# quantizer_main.net
KiCad netlist of a schematic drawn in EAGLE
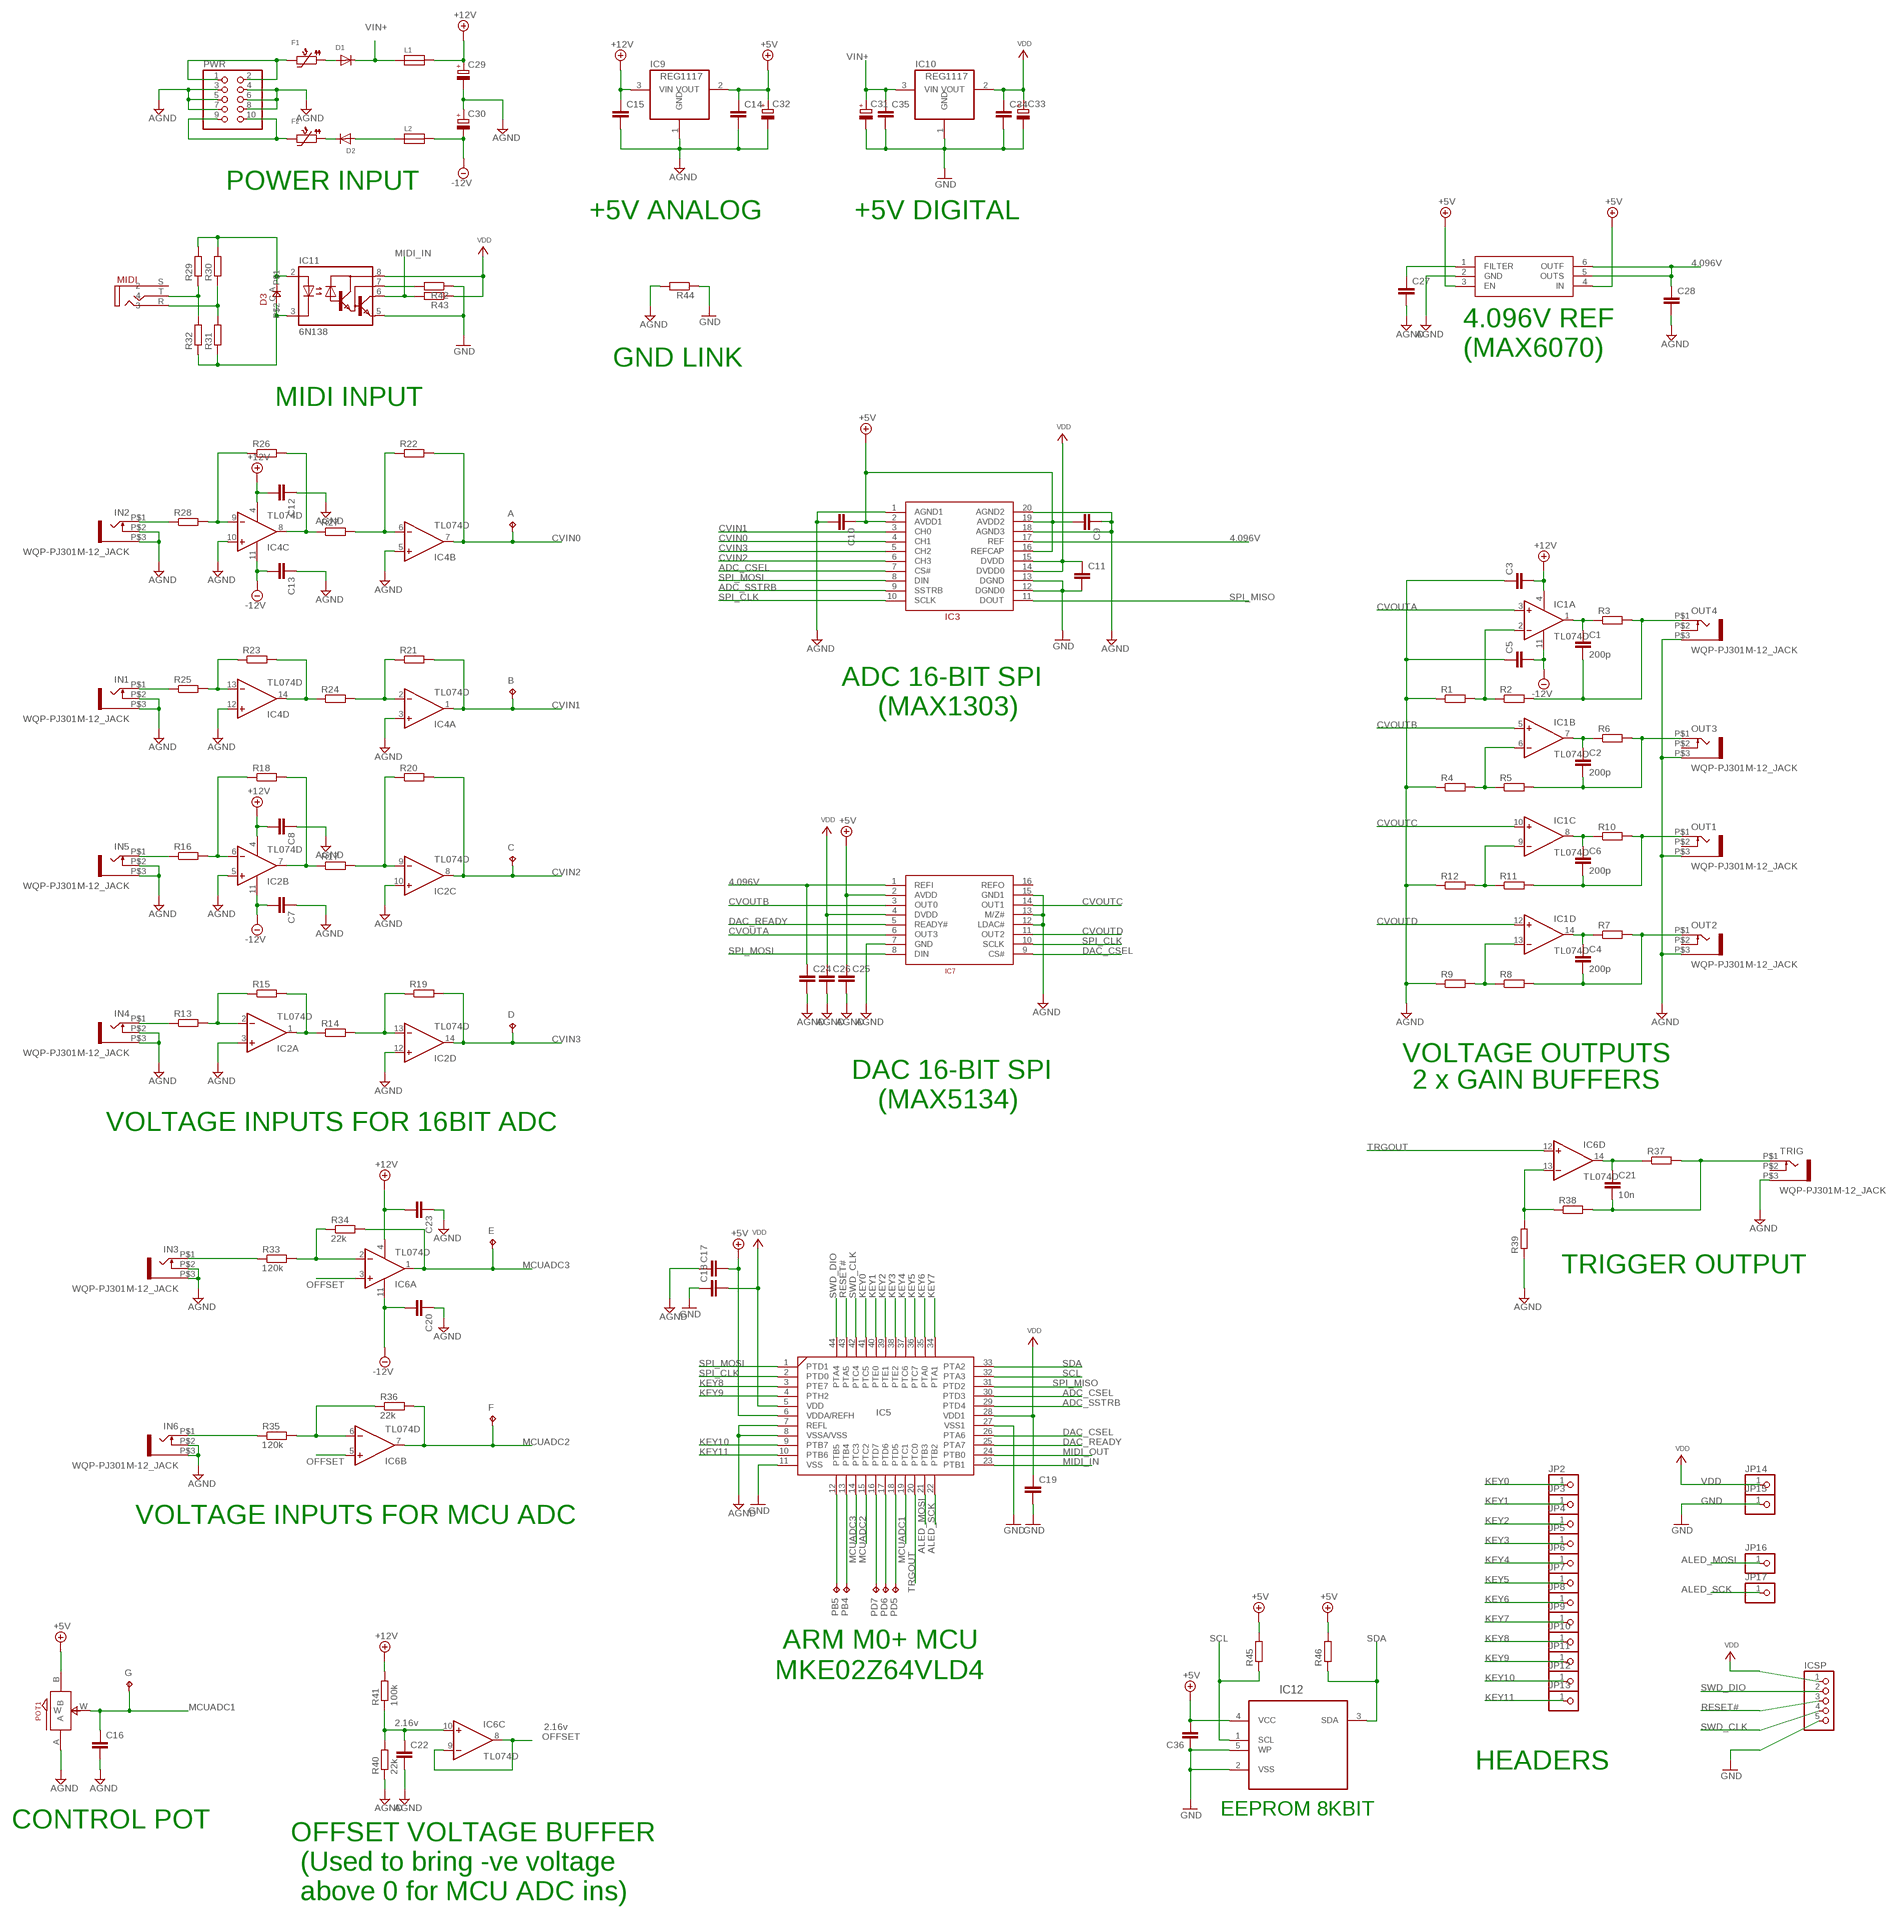
[diagram p0: schematic, sheet 1]

(export (version "E")
  (design (tool "Eeschema 10.0.6"))
  (components
    (comp (ref "A")
      (value "TPB1,27")
      (footprint "eagle-import:B1,27")
      (libsource (lib "eagle-import") (part "TPB1,27"))
    )
    (comp (ref "B")
      (value "TPB1,27")
      (footprint "eagle-import:B1,27")
      (libsource (lib "eagle-import") (part "TPB1,27"))
    )
    (comp (ref "C")
      (value "TPB1,27")
      (footprint "eagle-import:B1,27")
      (libsource (lib "eagle-import") (part "TPB1,27"))
    )
    (comp (ref "C1")
      (value "200p")
      (footprint "eagle-import:C0805")
      (libsource (lib "eagle-import") (part "C-EUC0805"))
    )
    (comp (ref "C2")
      (value "200p")
      (footprint "eagle-import:C0805")
      (libsource (lib "eagle-import") (part "C-EUC0805"))
    )
    (comp (ref "C3")
      (value "C-EUC0805")
      (footprint "eagle-import:C0805")
      (libsource (lib "eagle-import") (part "C-EUC0805"))
    )
    (comp (ref "C4")
      (value "200p")
      (footprint "eagle-import:C0805")
      (libsource (lib "eagle-import") (part "C-EUC0805"))
    )
    (comp (ref "C5")
      (value "C-EUC0805")
      (footprint "eagle-import:C0805")
      (libsource (lib "eagle-import") (part "C-EUC0805"))
    )
    (comp (ref "C6")
      (value "200p")
      (footprint "eagle-import:C0805")
      (libsource (lib "eagle-import") (part "C-EUC0805"))
    )
    (comp (ref "C7")
      (value "C-EUC0805")
      (footprint "eagle-import:C0805")
      (libsource (lib "eagle-import") (part "C-EUC0805"))
    )
    (comp (ref "C8")
      (value "C-EUC0805")
      (footprint "eagle-import:C0805")
      (libsource (lib "eagle-import") (part "C-EUC0805"))
    )
    (comp (ref "C9")
      (value "C-EUC0805")
      (footprint "eagle-import:C0805")
      (libsource (lib "eagle-import") (part "C-EUC0805"))
    )
    (comp (ref "C10")
      (value "C-EUC0805")
      (footprint "eagle-import:C0805")
      (libsource (lib "eagle-import") (part "C-EUC0805"))
    )
    (comp (ref "C11")
      (value "C-EUC0805")
      (footprint "eagle-import:C0805")
      (libsource (lib "eagle-import") (part "C-EUC0805"))
    )
    (comp (ref "C12")
      (value "C-EUC0805")
      (footprint "eagle-import:C0805")
      (libsource (lib "eagle-import") (part "C-EUC0805"))
    )
    (comp (ref "C13")
      (value "C-EUC0805")
      (footprint "eagle-import:C0805")
      (libsource (lib "eagle-import") (part "C-EUC0805"))
    )
    (comp (ref "C14")
      (value "C-EUC0805")
      (footprint "eagle-import:C0805")
      (libsource (lib "eagle-import") (part "C-EUC0805"))
    )
    (comp (ref "C15")
      (value "C-EUC0805")
      (footprint "eagle-import:C0805")
      (libsource (lib "eagle-import") (part "C-EUC0805"))
    )
    (comp (ref "C16")
      (value "C-EUC0805")
      (footprint "eagle-import:C0805")
      (libsource (lib "eagle-import") (part "C-EUC0805"))
    )
    (comp (ref "C17")
      (value "C-EUC0805")
      (footprint "eagle-import:C0805")
      (libsource (lib "eagle-import") (part "C-EUC0805"))
    )
    (comp (ref "C18")
      (value "C-EUC0805")
      (footprint "eagle-import:C0805")
      (libsource (lib "eagle-import") (part "C-EUC0805"))
    )
    (comp (ref "C19")
      (value "C-EUC0805")
      (footprint "eagle-import:C0805")
      (libsource (lib "eagle-import") (part "C-EUC0805"))
    )
    (comp (ref "C20")
      (value "C-EUC0805")
      (footprint "eagle-import:C0805")
      (libsource (lib "eagle-import") (part "C-EUC0805"))
    )
    (comp (ref "C21")
      (value "10n")
      (footprint "eagle-import:C0805")
      (libsource (lib "eagle-import") (part "C-EUC0805"))
    )
    (comp (ref "C22")
      (value "C-EUC0805")
      (footprint "eagle-import:C0805")
      (libsource (lib "eagle-import") (part "C-EUC0805"))
    )
    (comp (ref "C23")
      (value "C-EUC0805")
      (footprint "eagle-import:C0805")
      (libsource (lib "eagle-import") (part "C-EUC0805"))
    )
    (comp (ref "C24")
      (value "C-EUC0805")
      (footprint "eagle-import:C0805")
      (libsource (lib "eagle-import") (part "C-EUC0805"))
    )
    (comp (ref "C25")
      (value "C-EUC0805")
      (footprint "eagle-import:C0805")
      (libsource (lib "eagle-import") (part "C-EUC0805"))
    )
    (comp (ref "C26")
      (value "C-EUC0805")
      (footprint "eagle-import:C0805")
      (libsource (lib "eagle-import") (part "C-EUC0805"))
    )
    (comp (ref "C27")
      (value "C-EUC0805")
      (footprint "eagle-import:C0805")
      (libsource (lib "eagle-import") (part "C-EUC0805"))
    )
    (comp (ref "C28")
      (value "C-EUC0805")
      (footprint "eagle-import:C0805")
      (libsource (lib "eagle-import") (part "C-EUC0805"))
    )
    (comp (ref "C29")
      (value "CPOL-EUE2-5")
      (footprint "eagle-import:E2-5")
      (libsource (lib "eagle-import") (part "CPOL-EUE2-5"))
    )
    (comp (ref "C30")
      (value "CPOL-EUE2-5")
      (footprint "eagle-import:E2-5")
      (libsource (lib "eagle-import") (part "CPOL-EUE2-5"))
    )
    (comp (ref "C31")
      (value "CPOL-EUE2-5")
      (footprint "eagle-import:E2-5")
      (libsource (lib "eagle-import") (part "CPOL-EUE2-5"))
    )
    (comp (ref "C32")
      (value "CPOL-EUE2-5")
      (footprint "eagle-import:E2-5")
      (libsource (lib "eagle-import") (part "CPOL-EUE2-5"))
    )
    (comp (ref "C33")
      (value "CPOL-EUE2-5")
      (footprint "eagle-import:E2-5")
      (libsource (lib "eagle-import") (part "CPOL-EUE2-5"))
    )
    (comp (ref "C34")
      (value "C-EUC0805")
      (footprint "eagle-import:C0805")
      (libsource (lib "eagle-import") (part "C-EUC0805"))
    )
    (comp (ref "C35")
      (value "C-EUC0805")
      (footprint "eagle-import:C0805")
      (libsource (lib "eagle-import") (part "C-EUC0805"))
    )
    (comp (ref "C36")
      (value "C-EUC0805")
      (footprint "eagle-import:C0805")
      (libsource (lib "eagle-import") (part "resistor_C-EUC0805"))
    )
    (comp (ref "D")
      (value "TPB1,27")
      (footprint "eagle-import:B1,27")
      (libsource (lib "eagle-import") (part "TPB1,27"))
    )
    (comp (ref "D1")
      (value "DIODESOD-123")
      (footprint "eagle-import:SOD-123")
      (libsource (lib "eagle-import") (part "DIODESOD-123"))
    )
    (comp (ref "D2")
      (value "DIODESOD-123")
      (footprint "eagle-import:SOD-123")
      (libsource (lib "eagle-import") (part "DIODESOD-123"))
    )
    (comp (ref "D3")
      (value "0805DIODE")
      (footprint "eagle-import:0805DIODE")
      (libsource (lib "eagle-import") (part "0805DIODE"))
    )
    (comp (ref "E")
      (value "TPB1,27")
      (footprint "eagle-import:B1,27")
      (libsource (lib "eagle-import") (part "TPB1,27"))
    )
    (comp (ref "F")
      (value "TPB1,27")
      (footprint "eagle-import:B1,27")
      (libsource (lib "eagle-import") (part "TPB1,27"))
    )
    (comp (ref "F1")
      (value "PTC1206")
      (footprint "eagle-import:1206")
      (libsource (lib "eagle-import") (part "PTC1206"))
    )
    (comp (ref "F2")
      (value "PTC1206")
      (footprint "eagle-import:1206")
      (libsource (lib "eagle-import") (part "PTC1206"))
    )
    (comp (ref "G")
      (value "TPB1,27")
      (footprint "eagle-import:B1,27")
      (libsource (lib "eagle-import") (part "TPB1,27"))
    )
    (comp (ref "IC1")
      (value "TL074D")
      (footprint "eagle-import:SO14")
      (libsource (lib "eagle-import") (part "TL074D"))
    )
    (comp (ref "IC2")
      (value "TL074D")
      (footprint "eagle-import:SO14")
      (libsource (lib "eagle-import") (part "TL074D"))
    )
    (comp (ref "IC3")
      (value "MAX1303_ADC")
      (footprint "eagle-import:TSSOP20")
      (libsource (lib "eagle-import") (part "MAX1303_ADC"))
    )
    (comp (ref "IC4")
      (value "TL074D")
      (footprint "eagle-import:SO14")
      (libsource (lib "eagle-import") (part "TL074D"))
    )
    (comp (ref "IC5")
      (value "MKE02_44PIN")
      (footprint "eagle-import:TQFP44")
      (libsource (lib "eagle-import") (part "MKE02_44PIN"))
    )
    (comp (ref "IC6")
      (value "TL074D")
      (footprint "eagle-import:SO14")
      (libsource (lib "eagle-import") (part "TL074D"))
    )
    (comp (ref "IC7")
      (value "MAX5134_DAC")
      (footprint "eagle-import:TSSOP16")
      (libsource (lib "eagle-import") (part "MAX5134_DAC"))
    )
    (comp (ref "IC8")
      (value "MAX6070")
      (footprint "eagle-import:SOT23-6")
      (libsource (lib "eagle-import") (part "MAX6070"))
    )
    (comp (ref "IC9")
      (value "REG1117")
      (footprint "eagle-import:SOT223")
      (libsource (lib "eagle-import") (part "REG1117"))
    )
    (comp (ref "IC10")
      (value "REG1117")
      (footprint "eagle-import:SOT223")
      (libsource (lib "eagle-import") (part "REG1117"))
    )
    (comp (ref "IC11")
      (value "6N138")
      (footprint "eagle-import:DIL08")
      (fields (field (name "MF") "VISHAY/TELEFUNKEN"))
      (libsource (lib "eagle-import") (part "6N138"))
    )
    (comp (ref "IC12")
      (value "24LC_16BT-I/OT")
      (footprint "eagle-import:SOT95P290X145-5N")
      (fields (field (name "MPN") "24LC16BT-I/OT "))
      (libsource (lib "eagle-import") (part "24LC_16BT-I/OT"))
    )
    (comp (ref "ICSP")
      (value "PINHD-1X5")
      (footprint "eagle-import:1X05")
      (libsource (lib "eagle-import") (part "PINHD-1X5"))
    )
    (comp (ref "IN1")
      (value "WQP-PJ301M-12_JACK")
      (footprint "eagle-import:WQP-PJ301M-12_JACK")
      (libsource (lib "eagle-import") (part "WQP-PJ301M-12_JACK"))
    )
    (comp (ref "IN2")
      (value "WQP-PJ301M-12_JACK")
      (footprint "eagle-import:WQP-PJ301M-12_JACK")
      (libsource (lib "eagle-import") (part "WQP-PJ301M-12_JACK"))
    )
    (comp (ref "IN3")
      (value "WQP-PJ301M-12_JACK")
      (footprint "eagle-import:WQP-PJ301M-12_JACK")
      (libsource (lib "eagle-import") (part "WQP-PJ301M-12_JACK"))
    )
    (comp (ref "IN4")
      (value "WQP-PJ301M-12_JACK")
      (footprint "eagle-import:WQP-PJ301M-12_JACK")
      (libsource (lib "eagle-import") (part "WQP-PJ301M-12_JACK"))
    )
    (comp (ref "IN5")
      (value "WQP-PJ301M-12_JACK")
      (footprint "eagle-import:WQP-PJ301M-12_JACK")
      (libsource (lib "eagle-import") (part "WQP-PJ301M-12_JACK"))
    )
    (comp (ref "IN6")
      (value "WQP-PJ301M-12_JACK")
      (footprint "eagle-import:WQP-PJ301M-12_JACK")
      (libsource (lib "eagle-import") (part "WQP-PJ301M-12_JACK"))
    )
    (comp (ref "JP2")
      (value "PINHD-1X1")
      (footprint "eagle-import:1X01")
      (libsource (lib "eagle-import") (part "PINHD-1X1"))
    )
    (comp (ref "JP3")
      (value "PINHD-1X1")
      (footprint "eagle-import:1X01")
      (libsource (lib "eagle-import") (part "PINHD-1X1"))
    )
    (comp (ref "JP4")
      (value "PINHD-1X1")
      (footprint "eagle-import:1X01")
      (libsource (lib "eagle-import") (part "PINHD-1X1"))
    )
    (comp (ref "JP5")
      (value "PINHD-1X1")
      (footprint "eagle-import:1X01")
      (libsource (lib "eagle-import") (part "PINHD-1X1"))
    )
    (comp (ref "JP6")
      (value "PINHD-1X1")
      (footprint "eagle-import:1X01")
      (libsource (lib "eagle-import") (part "PINHD-1X1"))
    )
    (comp (ref "JP7")
      (value "PINHD-1X1")
      (footprint "eagle-import:1X01")
      (libsource (lib "eagle-import") (part "PINHD-1X1"))
    )
    (comp (ref "JP8")
      (value "PINHD-1X1")
      (footprint "eagle-import:1X01")
      (libsource (lib "eagle-import") (part "PINHD-1X1"))
    )
    (comp (ref "JP9")
      (value "PINHD-1X1")
      (footprint "eagle-import:1X01")
      (libsource (lib "eagle-import") (part "PINHD-1X1"))
    )
    (comp (ref "JP10")
      (value "PINHD-1X1")
      (footprint "eagle-import:1X01")
      (libsource (lib "eagle-import") (part "PINHD-1X1"))
    )
    (comp (ref "JP11")
      (value "PINHD-1X1")
      (footprint "eagle-import:1X01")
      (libsource (lib "eagle-import") (part "PINHD-1X1"))
    )
    (comp (ref "JP12")
      (value "PINHD-1X1")
      (footprint "eagle-import:1X01")
      (libsource (lib "eagle-import") (part "PINHD-1X1"))
    )
    (comp (ref "JP13")
      (value "PINHD-1X1")
      (footprint "eagle-import:1X01")
      (libsource (lib "eagle-import") (part "PINHD-1X1"))
    )
    (comp (ref "JP14")
      (value "PINHD-1X1")
      (footprint "eagle-import:1X01")
      (libsource (lib "eagle-import") (part "PINHD-1X1"))
    )
    (comp (ref "JP15")
      (value "PINHD-1X1")
      (footprint "eagle-import:1X01")
      (libsource (lib "eagle-import") (part "PINHD-1X1"))
    )
    (comp (ref "JP16")
      (value "PINHD-1X1")
      (footprint "eagle-import:1X01")
      (libsource (lib "eagle-import") (part "PINHD-1X1"))
    )
    (comp (ref "JP17")
      (value "PINHD-1X1")
      (footprint "eagle-import:1X01")
      (libsource (lib "eagle-import") (part "PINHD-1X1"))
    )
    (comp (ref "L1")
      (value "FERRITE")
      (footprint "eagle-import:0603")
      (libsource (lib "eagle-import") (part "FERRITE"))
    )
    (comp (ref "L2")
      (value "FERRITE")
      (footprint "eagle-import:0603")
      (libsource (lib "eagle-import") (part "FERRITE"))
    )
    (comp (ref "MIDI")
      (value "VERTICAL_3_5MM_SOCKETTHONK")
      (footprint "eagle-import:PJ301CM")
      (libsource (lib "eagle-import") (part "VERTICAL_3_5MM_SOCKETTHONK"))
    )
    (comp (ref "OUT1")
      (value "WQP-PJ301M-12_JACK")
      (footprint "eagle-import:WQP-PJ301M-12_JACK")
      (libsource (lib "eagle-import") (part "WQP-PJ301M-12_JACK"))
    )
    (comp (ref "OUT2")
      (value "WQP-PJ301M-12_JACK")
      (footprint "eagle-import:WQP-PJ301M-12_JACK")
      (libsource (lib "eagle-import") (part "WQP-PJ301M-12_JACK"))
    )
    (comp (ref "OUT3")
      (value "WQP-PJ301M-12_JACK")
      (footprint "eagle-import:WQP-PJ301M-12_JACK")
      (libsource (lib "eagle-import") (part "WQP-PJ301M-12_JACK"))
    )
    (comp (ref "OUT4")
      (value "WQP-PJ301M-12_JACK")
      (footprint "eagle-import:WQP-PJ301M-12_JACK")
      (libsource (lib "eagle-import") (part "WQP-PJ301M-12_JACK"))
    )
    (comp (ref "PB4")
      (value "TPB1,27")
      (footprint "eagle-import:B1,27")
      (libsource (lib "eagle-import") (part "TPB1,27"))
    )
    (comp (ref "PB5")
      (value "TPB1,27")
      (footprint "eagle-import:B1,27")
      (libsource (lib "eagle-import") (part "TPB1,27"))
    )
    (comp (ref "PD5")
      (value "TPB1,27")
      (footprint "eagle-import:B1,27")
      (libsource (lib "eagle-import") (part "TPB1,27"))
    )
    (comp (ref "PD6")
      (value "TPB1,27")
      (footprint "eagle-import:B1,27")
      (libsource (lib "eagle-import") (part "TPB1,27"))
    )
    (comp (ref "PD7")
      (value "TPB1,27")
      (footprint "eagle-import:B1,27")
      (libsource (lib "eagle-import") (part "TPB1,27"))
    )
    (comp (ref "POT1")
      (value "ALPS_POT_SMALL")
      (footprint "eagle-import:SMALL_ALPS_POT")
      (libsource (lib "eagle-import") (part "ALPS_POT_SMALL"))
    )
    (comp (ref "PWR")
      (value "PINHD-2X5")
      (footprint "eagle-import:2X05")
      (libsource (lib "eagle-import") (part "PINHD-2X5"))
    )
    (comp (ref "R1")
      (value "R-EU_R0805")
      (footprint "eagle-import:R0805")
      (libsource (lib "eagle-import") (part "R-EU_R0805"))
    )
    (comp (ref "R2")
      (value "R-EU_R0805")
      (footprint "eagle-import:R0805")
      (libsource (lib "eagle-import") (part "R-EU_R0805"))
    )
    (comp (ref "R3")
      (value "R-EU_R0805")
      (footprint "eagle-import:R0805")
      (libsource (lib "eagle-import") (part "R-EU_R0805"))
    )
    (comp (ref "R4")
      (value "R-EU_R0805")
      (footprint "eagle-import:R0805")
      (libsource (lib "eagle-import") (part "R-EU_R0805"))
    )
    (comp (ref "R5")
      (value "R-EU_R0805")
      (footprint "eagle-import:R0805")
      (libsource (lib "eagle-import") (part "R-EU_R0805"))
    )
    (comp (ref "R6")
      (value "R-EU_R0805")
      (footprint "eagle-import:R0805")
      (libsource (lib "eagle-import") (part "R-EU_R0805"))
    )
    (comp (ref "R7")
      (value "R-EU_R0805")
      (footprint "eagle-import:R0805")
      (libsource (lib "eagle-import") (part "R-EU_R0805"))
    )
    (comp (ref "R8")
      (value "R-EU_R0805")
      (footprint "eagle-import:R0805")
      (libsource (lib "eagle-import") (part "R-EU_R0805"))
    )
    (comp (ref "R9")
      (value "R-EU_R0805")
      (footprint "eagle-import:R0805")
      (libsource (lib "eagle-import") (part "R-EU_R0805"))
    )
    (comp (ref "R10")
      (value "R-EU_R0805")
      (footprint "eagle-import:R0805")
      (libsource (lib "eagle-import") (part "R-EU_R0805"))
    )
    (comp (ref "R11")
      (value "R-EU_R0805")
      (footprint "eagle-import:R0805")
      (libsource (lib "eagle-import") (part "R-EU_R0805"))
    )
    (comp (ref "R12")
      (value "R-EU_R0805")
      (footprint "eagle-import:R0805")
      (libsource (lib "eagle-import") (part "R-EU_R0805"))
    )
    (comp (ref "R13")
      (value "R-EU_R0805")
      (footprint "eagle-import:R0805")
      (libsource (lib "eagle-import") (part "R-EU_R0805"))
    )
    (comp (ref "R14")
      (value "R-EU_R0805")
      (footprint "eagle-import:R0805")
      (libsource (lib "eagle-import") (part "R-EU_R0805"))
    )
    (comp (ref "R15")
      (value "R-EU_R0805")
      (footprint "eagle-import:R0805")
      (libsource (lib "eagle-import") (part "R-EU_R0805"))
    )
    (comp (ref "R16")
      (value "R-EU_R0805")
      (footprint "eagle-import:R0805")
      (libsource (lib "eagle-import") (part "R-EU_R0805"))
    )
    (comp (ref "R17")
      (value "R-EU_R0805")
      (footprint "eagle-import:R0805")
      (libsource (lib "eagle-import") (part "R-EU_R0805"))
    )
    (comp (ref "R18")
      (value "R-EU_R0805")
      (footprint "eagle-import:R0805")
      (libsource (lib "eagle-import") (part "R-EU_R0805"))
    )
    (comp (ref "R19")
      (value "R-EU_R0805")
      (footprint "eagle-import:R0805")
      (libsource (lib "eagle-import") (part "R-EU_R0805"))
    )
    (comp (ref "R20")
      (value "R-EU_R0805")
      (footprint "eagle-import:R0805")
      (libsource (lib "eagle-import") (part "R-EU_R0805"))
    )
    (comp (ref "R21")
      (value "R-EU_R0805")
      (footprint "eagle-import:R0805")
      (libsource (lib "eagle-import") (part "R-EU_R0805"))
    )
    (comp (ref "R22")
      (value "R-EU_R0805")
      (footprint "eagle-import:R0805")
      (libsource (lib "eagle-import") (part "R-EU_R0805"))
    )
    (comp (ref "R23")
      (value "R-EU_R0805")
      (footprint "eagle-import:R0805")
      (libsource (lib "eagle-import") (part "R-EU_R0805"))
    )
    (comp (ref "R24")
      (value "R-EU_R0805")
      (footprint "eagle-import:R0805")
      (libsource (lib "eagle-import") (part "R-EU_R0805"))
    )
    (comp (ref "R25")
      (value "R-EU_R0805")
      (footprint "eagle-import:R0805")
      (libsource (lib "eagle-import") (part "R-EU_R0805"))
    )
    (comp (ref "R26")
      (value "R-EU_R0805")
      (footprint "eagle-import:R0805")
      (libsource (lib "eagle-import") (part "R-EU_R0805"))
    )
    (comp (ref "R27")
      (value "R-EU_R0805")
      (footprint "eagle-import:R0805")
      (libsource (lib "eagle-import") (part "R-EU_R0805"))
    )
    (comp (ref "R28")
      (value "R-EU_R0805")
      (footprint "eagle-import:R0805")
      (libsource (lib "eagle-import") (part "R-EU_R0805"))
    )
    (comp (ref "R29")
      (value "R-EU_R0805")
      (footprint "eagle-import:R0805")
      (libsource (lib "eagle-import") (part "R-EU_R0805"))
    )
    (comp (ref "R30")
      (value "R-EU_R0805")
      (footprint "eagle-import:R0805")
      (libsource (lib "eagle-import") (part "R-EU_R0805"))
    )
    (comp (ref "R31")
      (value "R-EU_R0805")
      (footprint "eagle-import:R0805")
      (libsource (lib "eagle-import") (part "R-EU_R0805"))
    )
    (comp (ref "R32")
      (value "R-EU_R0805")
      (footprint "eagle-import:R0805")
      (libsource (lib "eagle-import") (part "R-EU_R0805"))
    )
    (comp (ref "R33")
      (value "120k")
      (footprint "eagle-import:R0805")
      (libsource (lib "eagle-import") (part "R-EU_R0805"))
    )
    (comp (ref "R34")
      (value "22k")
      (footprint "eagle-import:R0805")
      (libsource (lib "eagle-import") (part "R-EU_R0805"))
    )
    (comp (ref "R35")
      (value "120k")
      (footprint "eagle-import:R0805")
      (libsource (lib "eagle-import") (part "R-EU_R0805"))
    )
    (comp (ref "R36")
      (value "22k")
      (footprint "eagle-import:R0805")
      (libsource (lib "eagle-import") (part "R-EU_R0805"))
    )
    (comp (ref "R37")
      (value "R-EU_R0805")
      (footprint "eagle-import:R0805")
      (libsource (lib "eagle-import") (part "R-EU_R0805"))
    )
    (comp (ref "R38")
      (value "R-EU_R0805")
      (footprint "eagle-import:R0805")
      (libsource (lib "eagle-import") (part "R-EU_R0805"))
    )
    (comp (ref "R39")
      (value "R-EU_R0805")
      (footprint "eagle-import:R0805")
      (libsource (lib "eagle-import") (part "R-EU_R0805"))
    )
    (comp (ref "R40")
      (value "22k")
      (footprint "eagle-import:R0805")
      (libsource (lib "eagle-import") (part "R-EU_R0805"))
    )
    (comp (ref "R41")
      (value "100k")
      (footprint "eagle-import:R0805")
      (libsource (lib "eagle-import") (part "R-EU_R0805"))
    )
    (comp (ref "R42")
      (value "R-EU_R0805")
      (footprint "eagle-import:R0805")
      (libsource (lib "eagle-import") (part "R-EU_R0805"))
    )
    (comp (ref "R43")
      (value "R-EU_R0805")
      (footprint "eagle-import:R0805")
      (libsource (lib "eagle-import") (part "R-EU_R0805"))
    )
    (comp (ref "R44")
      (value "R-EU_R0805")
      (footprint "eagle-import:R0805")
      (libsource (lib "eagle-import") (part "R-EU_R0805"))
    )
    (comp (ref "R45")
      (value "R-EU_R0805")
      (footprint "eagle-import:R0805")
      (libsource (lib "eagle-import") (part "R-EU_R0805"))
    )
    (comp (ref "R46")
      (value "R-EU_R0805")
      (footprint "eagle-import:R0805")
      (libsource (lib "eagle-import") (part "R-EU_R0805"))
    )
    (comp (ref "TRIG")
      (value "WQP-PJ301M-12_JACK")
      (footprint "eagle-import:WQP-PJ301M-12_JACK")
      (libsource (lib "eagle-import") (part "WQP-PJ301M-12_JACK"))
    )
  )
  (nets
    (net (code "1") (name "+5V") (class "Default")
      (node (ref "C10") (pin "1") (pinfunction "1_1") (pintype "passive"))
      (node (ref "C14") (pin "1") (pinfunction "1_1") (pintype "passive"))
      (node (ref "C17") (pin "2") (pinfunction "2_2") (pintype "passive"))
      (node (ref "C25") (pin "1") (pinfunction "1_1") (pintype "passive"))
      (node (ref "C32") (pin "+") (pinfunction "+_+") (pintype "passive"))
      (node (ref "C36") (pin "2") (pinfunction "2_2") (pintype "passive"))
      (node (ref "C9") (pin "2") (pinfunction "2_2") (pintype "passive"))
      (node (ref "IC12") (pin "4") (pinfunction "VCC_4") (pintype "power_in"))
      (node (ref "IC3") (pin "16") (pinfunction "REFCAP_16") (pintype "bidirectional"))
      (node (ref "IC3") (pin "19") (pinfunction "AVDD2_19") (pintype "bidirectional"))
      (node (ref "IC3") (pin "2") (pinfunction "AVDD1_2") (pintype "bidirectional"))
      (node (ref "IC5") (pin "6") (pinfunction "VDDA/REFH_6") (pintype "bidirectional"))
      (node (ref "IC7") (pin "2") (pinfunction "AVDD_2") (pintype "bidirectional"))
      (node (ref "IC8") (pin "3") (pinfunction "EN_3") (pintype "bidirectional"))
      (node (ref "IC8") (pin "4") (pinfunction "IN_4") (pintype "bidirectional"))
      (node (ref "IC9") (pin "2") (pinfunction "VOUT_2") (pintype "output"))
      (node (ref "POT1") (pin "B") (pinfunction "B_B") (pintype "bidirectional"))
      (node (ref "R45") (pin "2") (pinfunction "2_2") (pintype "passive"))
      (node (ref "R46") (pin "2") (pinfunction "2_2") (pintype "passive"))
    )
    (net (code "2") (name "+12V") (class "Default")
      (node (ref "C12") (pin "2") (pinfunction "2_2") (pintype "passive"))
      (node (ref "C15") (pin "1") (pinfunction "1_1") (pintype "passive"))
      (node (ref "C23") (pin "2") (pinfunction "2_2") (pintype "passive"))
      (node (ref "C29") (pin "+") (pinfunction "+_+") (pintype "passive"))
      (node (ref "C3") (pin "2") (pinfunction "2_2") (pintype "passive"))
      (node (ref "C8") (pin "2") (pinfunction "2_2") (pintype "passive"))
      (node (ref "IC1") (pin "4") (pinfunction "V+_4") (pintype "power_in"))
      (node (ref "IC2") (pin "4") (pinfunction "V+_4") (pintype "power_in"))
      (node (ref "IC4") (pin "4") (pinfunction "V+_4") (pintype "power_in"))
      (node (ref "IC6") (pin "4") (pinfunction "V+_4") (pintype "power_in"))
      (node (ref "IC9") (pin "3") (pinfunction "VIN_3") (pintype "input"))
      (node (ref "L1") (pin "2") (pinfunction "P$2_2") (pintype "bidirectional"))
      (node (ref "R41") (pin "2") (pinfunction "2_2") (pintype "passive"))
    )
    (net (code "3") (name "-12V") (class "Default")
      (node (ref "C13") (pin "2") (pinfunction "2_2") (pintype "passive"))
      (node (ref "C20") (pin "2") (pinfunction "2_2") (pintype "passive"))
      (node (ref "C30") (pin "-") (pinfunction "-_-") (pintype "passive"))
      (node (ref "C5") (pin "2") (pinfunction "2_2") (pintype "passive"))
      (node (ref "C7") (pin "2") (pinfunction "2_2") (pintype "passive"))
      (node (ref "IC1") (pin "11") (pinfunction "V-_11") (pintype "power_in"))
      (node (ref "IC2") (pin "11") (pinfunction "V-_11") (pintype "power_in"))
      (node (ref "IC4") (pin "11") (pinfunction "V-_11") (pintype "power_in"))
      (node (ref "IC6") (pin "11") (pinfunction "V-_11") (pintype "power_in"))
      (node (ref "L2") (pin "2") (pinfunction "P$2_2") (pintype "bidirectional"))
    )
    (net (code "4") (name "/4.096V") (class "Default")
      (node (ref "C24") (pin "1") (pinfunction "1_1") (pintype "passive"))
      (node (ref "C28") (pin "1") (pinfunction "1_1") (pintype "passive"))
      (node (ref "IC3") (pin "17") (pinfunction "REF_17") (pintype "bidirectional"))
      (node (ref "IC7") (pin "1") (pinfunction "REFI_1") (pintype "bidirectional"))
      (node (ref "IC8") (pin "5") (pinfunction "OUTS_5") (pintype "bidirectional"))
      (node (ref "IC8") (pin "6") (pinfunction "OUTF_6") (pintype "bidirectional"))
    )
    (net (code "5") (name "/ADC_CSEL") (class "Default")
      (node (ref "IC3") (pin "7") (pinfunction "CS#_7") (pintype "bidirectional"))
      (node (ref "IC5") (pin "30") (pinfunction "PTD3_30") (pintype "bidirectional"))
    )
    (net (code "6") (name "/ADC_SSTRB") (class "Default")
      (node (ref "IC3") (pin "9") (pinfunction "SSTRB_9") (pintype "bidirectional"))
      (node (ref "IC5") (pin "29") (pinfunction "PTD4_29") (pintype "bidirectional"))
    )
    (net (code "7") (name "/ALED_MOSI") (class "Default")
      (node (ref "IC5") (pin "21") (pinfunction "PTB3_21") (pintype "bidirectional"))
      (node (ref "JP16") (pin "1") (pinfunction "1_1") (pintype "passive"))
    )
    (net (code "8") (name "/ALED_SCK") (class "Default")
      (node (ref "IC5") (pin "22") (pinfunction "PTB2_22") (pintype "bidirectional"))
      (node (ref "JP17") (pin "1") (pinfunction "1_1") (pintype "passive"))
    )
    (net (code "9") (name "/CVIN0") (class "Default")
      (node (ref "A") (pin "TP") (pinfunction "TP_TP") (pintype "input"))
      (node (ref "IC3") (pin "4") (pinfunction "CH1_4") (pintype "bidirectional"))
      (node (ref "IC4") (pin "7") (pinfunction "OUT_7") (pintype "output"))
      (node (ref "R22") (pin "2") (pinfunction "2_2") (pintype "passive"))
    )
    (net (code "10") (name "/CVIN1") (class "Default")
      (node (ref "B") (pin "TP") (pinfunction "TP_TP") (pintype "input"))
      (node (ref "IC3") (pin "3") (pinfunction "CH0_3") (pintype "bidirectional"))
      (node (ref "IC4") (pin "1") (pinfunction "OUT_1") (pintype "output"))
      (node (ref "R21") (pin "2") (pinfunction "2_2") (pintype "passive"))
    )
    (net (code "11") (name "/CVIN2") (class "Default")
      (node (ref "C") (pin "TP") (pinfunction "TP_TP") (pintype "input"))
      (node (ref "IC2") (pin "8") (pinfunction "OUT_8") (pintype "output"))
      (node (ref "IC3") (pin "6") (pinfunction "CH3_6") (pintype "bidirectional"))
      (node (ref "R20") (pin "2") (pinfunction "2_2") (pintype "passive"))
    )
    (net (code "12") (name "/CVIN3") (class "Default")
      (node (ref "D") (pin "TP") (pinfunction "TP_TP") (pintype "input"))
      (node (ref "IC2") (pin "14") (pinfunction "OUT_14") (pintype "output"))
      (node (ref "IC3") (pin "5") (pinfunction "CH2_5") (pintype "bidirectional"))
      (node (ref "R19") (pin "2") (pinfunction "2_2") (pintype "passive"))
    )
    (net (code "13") (name "/CVOUTA") (class "Default")
      (node (ref "IC1") (pin "3") (pinfunction "+IN_3") (pintype "input"))
      (node (ref "IC7") (pin "6") (pinfunction "OUT3_6") (pintype "bidirectional"))
    )
    (net (code "14") (name "/CVOUTB") (class "Default")
      (node (ref "IC1") (pin "5") (pinfunction "+IN_5") (pintype "input"))
      (node (ref "IC7") (pin "3") (pinfunction "OUT0_3") (pintype "bidirectional"))
    )
    (net (code "15") (name "/CVOUTC") (class "Default")
      (node (ref "IC1") (pin "10") (pinfunction "+IN_10") (pintype "input"))
      (node (ref "IC7") (pin "14") (pinfunction "OUT1_14") (pintype "bidirectional"))
    )
    (net (code "16") (name "/CVOUTD") (class "Default")
      (node (ref "IC1") (pin "12") (pinfunction "+IN_12") (pintype "input"))
      (node (ref "IC7") (pin "11") (pinfunction "OUT2_11") (pintype "bidirectional"))
    )
    (net (code "17") (name "/DAC_CSEL") (class "Default")
      (node (ref "IC5") (pin "26") (pinfunction "PTA6_26") (pintype "bidirectional"))
      (node (ref "IC7") (pin "9") (pinfunction "CS#_9") (pintype "bidirectional"))
    )
    (net (code "18") (name "/DAC_READY") (class "Default")
      (node (ref "IC5") (pin "25") (pinfunction "PTA7_25") (pintype "bidirectional"))
      (node (ref "IC7") (pin "5") (pinfunction "READY#_5") (pintype "bidirectional"))
    )
    (net (code "19") (name "/KEY0") (class "Default")
      (node (ref "IC5") (pin "41") (pinfunction "PTC5_41") (pintype "bidirectional"))
      (node (ref "JP2") (pin "1") (pinfunction "1_1") (pintype "passive"))
    )
    (net (code "20") (name "/KEY1") (class "Default")
      (node (ref "IC5") (pin "40") (pinfunction "PTE0_40") (pintype "bidirectional"))
      (node (ref "JP3") (pin "1") (pinfunction "1_1") (pintype "passive"))
    )
    (net (code "21") (name "/KEY2") (class "Default")
      (node (ref "IC5") (pin "39") (pinfunction "PTE1_39") (pintype "bidirectional"))
      (node (ref "JP4") (pin "1") (pinfunction "1_1") (pintype "passive"))
    )
    (net (code "22") (name "/KEY3") (class "Default")
      (node (ref "IC5") (pin "38") (pinfunction "PTE2_38") (pintype "bidirectional"))
      (node (ref "JP5") (pin "1") (pinfunction "1_1") (pintype "passive"))
    )
    (net (code "23") (name "/KEY4") (class "Default")
      (node (ref "IC5") (pin "37") (pinfunction "PTC6_37") (pintype "bidirectional"))
      (node (ref "JP6") (pin "1") (pinfunction "1_1") (pintype "passive"))
    )
    (net (code "24") (name "/KEY5") (class "Default")
      (node (ref "IC5") (pin "36") (pinfunction "PTC7_36") (pintype "bidirectional"))
      (node (ref "JP7") (pin "1") (pinfunction "1_1") (pintype "passive"))
    )
    (net (code "25") (name "/KEY6") (class "Default")
      (node (ref "IC5") (pin "35") (pinfunction "PTA0_35") (pintype "bidirectional"))
      (node (ref "JP8") (pin "1") (pinfunction "1_1") (pintype "passive"))
    )
    (net (code "26") (name "/KEY7") (class "Default")
      (node (ref "IC5") (pin "34") (pinfunction "PTA1_34") (pintype "bidirectional"))
      (node (ref "JP9") (pin "1") (pinfunction "1_1") (pintype "passive"))
    )
    (net (code "27") (name "/KEY8") (class "Default")
      (node (ref "IC5") (pin "3") (pinfunction "PTE7_3") (pintype "bidirectional"))
      (node (ref "JP10") (pin "1") (pinfunction "1_1") (pintype "passive"))
    )
    (net (code "28") (name "/KEY9") (class "Default")
      (node (ref "IC5") (pin "4") (pinfunction "PTH2_4") (pintype "bidirectional"))
      (node (ref "JP11") (pin "1") (pinfunction "1_1") (pintype "passive"))
    )
    (net (code "29") (name "/KEY10") (class "Default")
      (node (ref "IC5") (pin "9") (pinfunction "PTB7_9") (pintype "bidirectional"))
      (node (ref "JP12") (pin "1") (pinfunction "1_1") (pintype "passive"))
    )
    (net (code "30") (name "/KEY11") (class "Default")
      (node (ref "IC5") (pin "10") (pinfunction "PTB6_10") (pintype "bidirectional"))
      (node (ref "JP13") (pin "1") (pinfunction "1_1") (pintype "passive"))
    )
    (net (code "31") (name "/MCUADC1") (class "Default")
      (node (ref "C16") (pin "1") (pinfunction "1_1") (pintype "passive"))
      (node (ref "G") (pin "TP") (pinfunction "TP_TP") (pintype "input"))
      (node (ref "IC5") (pin "19") (pinfunction "PTC1_19") (pintype "bidirectional"))
      (node (ref "POT1") (pin "W") (pinfunction "W_W") (pintype "bidirectional"))
    )
    (net (code "32") (name "/MCUADC2") (class "Default")
      (node (ref "F") (pin "TP") (pinfunction "TP_TP") (pintype "input"))
      (node (ref "IC5") (pin "15") (pinfunction "PTC2_15") (pintype "bidirectional"))
      (node (ref "IC6") (pin "7") (pinfunction "OUT_7") (pintype "output"))
      (node (ref "R36") (pin "2") (pinfunction "2_2") (pintype "passive"))
    )
    (net (code "33") (name "/MCUADC3") (class "Default")
      (node (ref "E") (pin "TP") (pinfunction "TP_TP") (pintype "input"))
      (node (ref "IC5") (pin "14") (pinfunction "PTC3_14") (pintype "bidirectional"))
      (node (ref "IC6") (pin "1") (pinfunction "OUT_1") (pintype "output"))
      (node (ref "R34") (pin "2") (pinfunction "2_2") (pintype "passive"))
    )
    (net (code "34") (name "/MIDI_IN") (class "Default")
      (node (ref "IC11") (pin "6") (pinfunction "VO_6") (pintype "passive"))
      (node (ref "IC5") (pin "23") (pinfunction "PTB1_23") (pintype "bidirectional"))
      (node (ref "R43") (pin "2") (pinfunction "2_2") (pintype "passive"))
    )
    (net (code "35") (name "/MIDI_OUT") (class "Default")
      (node (ref "IC5") (pin "24") (pinfunction "PTB0_24") (pintype "bidirectional"))
    )
    (net (code "36") (name "/OFFSET") (class "Default")
      (node (ref "IC6") (pin "3") (pinfunction "+IN_3") (pintype "input"))
      (node (ref "IC6") (pin "5") (pinfunction "+IN_5") (pintype "input"))
      (node (ref "IC6") (pin "8") (pinfunction "OUT_8") (pintype "output"))
      (node (ref "IC6") (pin "9") (pinfunction "-IN_9") (pintype "input"))
    )
    (net (code "37") (name "/RESET#") (class "Default")
      (node (ref "IC5") (pin "43") (pinfunction "PTA5_43") (pintype "bidirectional"))
      (node (ref "ICSP") (pin "3") (pinfunction "3_3") (pintype "passive"))
    )
    (net (code "38") (name "/SCL") (class "Default")
      (node (ref "IC12") (pin "1") (pinfunction "SCL_1") (pintype "input"))
      (node (ref "IC5") (pin "32") (pinfunction "PTA3_32") (pintype "bidirectional"))
      (node (ref "R45") (pin "1") (pinfunction "1_1") (pintype "passive"))
    )
    (net (code "39") (name "/SDA") (class "Default")
      (node (ref "IC12") (pin "3") (pinfunction "SDA_3") (pintype "bidirectional"))
      (node (ref "IC5") (pin "33") (pinfunction "PTA2_33") (pintype "bidirectional"))
      (node (ref "R46") (pin "1") (pinfunction "1_1") (pintype "passive"))
    )
    (net (code "40") (name "/SPI_CLK") (class "Default")
      (node (ref "IC3") (pin "10") (pinfunction "SCLK_10") (pintype "bidirectional"))
      (node (ref "IC5") (pin "2") (pinfunction "PTD0_2") (pintype "bidirectional"))
      (node (ref "IC7") (pin "10") (pinfunction "SCLK_10") (pintype "bidirectional"))
    )
    (net (code "41") (name "/SPI_MISO") (class "Default")
      (node (ref "IC3") (pin "11") (pinfunction "DOUT_11") (pintype "bidirectional"))
      (node (ref "IC5") (pin "31") (pinfunction "PTD2_31") (pintype "bidirectional"))
    )
    (net (code "42") (name "/SPI_MOSI") (class "Default")
      (node (ref "IC3") (pin "8") (pinfunction "DIN_8") (pintype "bidirectional"))
      (node (ref "IC5") (pin "1") (pinfunction "PTD1_1") (pintype "bidirectional"))
      (node (ref "IC7") (pin "8") (pinfunction "DIN_8") (pintype "bidirectional"))
    )
    (net (code "43") (name "/SWD_CLK") (class "Default")
      (node (ref "IC5") (pin "42") (pinfunction "PTC4_42") (pintype "bidirectional"))
      (node (ref "ICSP") (pin "4") (pinfunction "4_4") (pintype "passive"))
    )
    (net (code "44") (name "/SWD_DIO") (class "Default")
      (node (ref "IC5") (pin "44") (pinfunction "PTA4_44") (pintype "bidirectional"))
      (node (ref "ICSP") (pin "2") (pinfunction "2_2") (pintype "passive"))
    )
    (net (code "45") (name "/TRGOUT") (class "Default")
      (node (ref "IC5") (pin "20") (pinfunction "PTC0_20") (pintype "bidirectional"))
      (node (ref "IC6") (pin "12") (pinfunction "+IN_12") (pintype "input"))
    )
    (net (code "46") (name "/VIN+") (class "Default")
      (node (ref "C31") (pin "+") (pinfunction "+_+") (pintype "passive"))
      (node (ref "C35") (pin "1") (pinfunction "1_1") (pintype "passive"))
      (node (ref "D1") (pin "C") (pinfunction "C_C") (pintype "passive"))
      (node (ref "IC10") (pin "3") (pinfunction "VIN_3") (pintype "input"))
      (node (ref "L1") (pin "1") (pinfunction "P$1_1") (pintype "bidirectional"))
    )
    (net (code "47") (name "AGND") (class "Default")
      (node (ref "C10") (pin "2") (pinfunction "2_2") (pintype "passive"))
      (node (ref "C12") (pin "1") (pinfunction "1_1") (pintype "passive"))
      (node (ref "C13") (pin "1") (pinfunction "1_1") (pintype "passive"))
      (node (ref "C14") (pin "2") (pinfunction "2_2") (pintype "passive"))
      (node (ref "C15") (pin "2") (pinfunction "2_2") (pintype "passive"))
      (node (ref "C16") (pin "2") (pinfunction "2_2") (pintype "passive"))
      (node (ref "C17") (pin "1") (pinfunction "1_1") (pintype "passive"))
      (node (ref "C20") (pin "1") (pinfunction "1_1") (pintype "passive"))
      (node (ref "C22") (pin "2") (pinfunction "2_2") (pintype "passive"))
      (node (ref "C23") (pin "1") (pinfunction "1_1") (pintype "passive"))
      (node (ref "C24") (pin "2") (pinfunction "2_2") (pintype "passive"))
      (node (ref "C25") (pin "2") (pinfunction "2_2") (pintype "passive"))
      (node (ref "C26") (pin "2") (pinfunction "2_2") (pintype "passive"))
      (node (ref "C27") (pin "2") (pinfunction "2_2") (pintype "passive"))
      (node (ref "C28") (pin "2") (pinfunction "2_2") (pintype "passive"))
      (node (ref "C29") (pin "-") (pinfunction "-_-") (pintype "passive"))
      (node (ref "C3") (pin "1") (pinfunction "1_1") (pintype "passive"))
      (node (ref "C30") (pin "+") (pinfunction "+_+") (pintype "passive"))
      (node (ref "C32") (pin "-") (pinfunction "-_-") (pintype "passive"))
      (node (ref "C5") (pin "1") (pinfunction "1_1") (pintype "passive"))
      (node (ref "C7") (pin "1") (pinfunction "1_1") (pintype "passive"))
      (node (ref "C8") (pin "1") (pinfunction "1_1") (pintype "passive"))
      (node (ref "C9") (pin "1") (pinfunction "1_1") (pintype "passive"))
      (node (ref "IC2") (pin "10") (pinfunction "+IN_10") (pintype "input"))
      (node (ref "IC2") (pin "12") (pinfunction "+IN_12") (pintype "input"))
      (node (ref "IC2") (pin "3") (pinfunction "+IN_3") (pintype "input"))
      (node (ref "IC2") (pin "5") (pinfunction "+IN_5") (pintype "input"))
      (node (ref "IC3") (pin "1") (pinfunction "AGND1_1") (pintype "bidirectional"))
      (node (ref "IC3") (pin "18") (pinfunction "AGND3_18") (pintype "bidirectional"))
      (node (ref "IC3") (pin "20") (pinfunction "AGND2_20") (pintype "bidirectional"))
      (node (ref "IC4") (pin "10") (pinfunction "+IN_10") (pintype "input"))
      (node (ref "IC4") (pin "12") (pinfunction "+IN_12") (pintype "input"))
      (node (ref "IC4") (pin "3") (pinfunction "+IN_3") (pintype "input"))
      (node (ref "IC4") (pin "5") (pinfunction "+IN_5") (pintype "input"))
      (node (ref "IC5") (pin "7") (pinfunction "REFL_7") (pintype "bidirectional"))
      (node (ref "IC5") (pin "8") (pinfunction "VSSA/VSS_8") (pintype "power_in"))
      (node (ref "IC7") (pin "12") (pinfunction "LDAC#_12") (pintype "bidirectional"))
      (node (ref "IC7") (pin "13") (pinfunction "M/Z#_13") (pintype "bidirectional"))
      (node (ref "IC7") (pin "15") (pinfunction "GND1_15") (pintype "bidirectional"))
      (node (ref "IC7") (pin "7") (pinfunction "GND_7") (pintype "bidirectional"))
      (node (ref "IC8") (pin "2") (pinfunction "GND_2") (pintype "bidirectional"))
      (node (ref "IC9") (pin "1") (pinfunction "GND_1") (pintype "power_in"))
      (node (ref "IN1") (pin "P$2") (pinfunction "3_P$2") (pintype "passive"))
      (node (ref "IN1") (pin "P$3") (pinfunction "1_P$3") (pintype "passive"))
      (node (ref "IN2") (pin "P$2") (pinfunction "3_P$2") (pintype "passive"))
      (node (ref "IN2") (pin "P$3") (pinfunction "1_P$3") (pintype "passive"))
      (node (ref "IN3") (pin "P$2") (pinfunction "3_P$2") (pintype "passive"))
      (node (ref "IN3") (pin "P$3") (pinfunction "1_P$3") (pintype "passive"))
      (node (ref "IN4") (pin "P$2") (pinfunction "3_P$2") (pintype "passive"))
      (node (ref "IN4") (pin "P$3") (pinfunction "1_P$3") (pintype "passive"))
      (node (ref "IN5") (pin "P$2") (pinfunction "3_P$2") (pintype "passive"))
      (node (ref "IN5") (pin "P$3") (pinfunction "1_P$3") (pintype "passive"))
      (node (ref "IN6") (pin "P$2") (pinfunction "3_P$2") (pintype "passive"))
      (node (ref "IN6") (pin "P$3") (pinfunction "1_P$3") (pintype "passive"))
      (node (ref "OUT1") (pin "P$3") (pinfunction "1_P$3") (pintype "passive"))
      (node (ref "OUT2") (pin "P$3") (pinfunction "1_P$3") (pintype "passive"))
      (node (ref "OUT3") (pin "P$3") (pinfunction "1_P$3") (pintype "passive"))
      (node (ref "OUT4") (pin "P$3") (pinfunction "1_P$3") (pintype "passive"))
      (node (ref "POT1") (pin "A") (pinfunction "A_A") (pintype "bidirectional"))
      (node (ref "PWR") (pin "3") (pinfunction "3_3") (pintype "passive"))
      (node (ref "PWR") (pin "4") (pinfunction "4_4") (pintype "passive"))
      (node (ref "PWR") (pin "5") (pinfunction "5_5") (pintype "passive"))
      (node (ref "PWR") (pin "6") (pinfunction "6_6") (pintype "passive"))
      (node (ref "PWR") (pin "7") (pinfunction "7_7") (pintype "passive"))
      (node (ref "PWR") (pin "8") (pinfunction "8_8") (pintype "passive"))
      (node (ref "R1") (pin "1") (pinfunction "1_1") (pintype "passive"))
      (node (ref "R12") (pin "1") (pinfunction "1_1") (pintype "passive"))
      (node (ref "R39") (pin "1") (pinfunction "1_1") (pintype "passive"))
      (node (ref "R4") (pin "1") (pinfunction "1_1") (pintype "passive"))
      (node (ref "R40") (pin "1") (pinfunction "1_1") (pintype "passive"))
      (node (ref "R44") (pin "2") (pinfunction "2_2") (pintype "passive"))
      (node (ref "R9") (pin "1") (pinfunction "1_1") (pintype "passive"))
      (node (ref "TRIG") (pin "P$3") (pinfunction "1_P$3") (pintype "passive"))
    )
    (net (code "48") (name "GND") (class "Default")
      (node (ref "C11") (pin "2") (pinfunction "2_2") (pintype "passive"))
      (node (ref "C18") (pin "1") (pinfunction "1_1") (pintype "passive"))
      (node (ref "C19") (pin "2") (pinfunction "2_2") (pintype "passive"))
      (node (ref "C31") (pin "-") (pinfunction "-_-") (pintype "passive"))
      (node (ref "C33") (pin "-") (pinfunction "-_-") (pintype "passive"))
      (node (ref "C34") (pin "2") (pinfunction "2_2") (pintype "passive"))
      (node (ref "C35") (pin "2") (pinfunction "2_2") (pintype "passive"))
      (node (ref "C36") (pin "1") (pinfunction "1_1") (pintype "passive"))
      (node (ref "IC10") (pin "1") (pinfunction "GND_1") (pintype "power_in"))
      (node (ref "IC11") (pin "5") (pinfunction "GND_5") (pintype "passive"))
      (node (ref "IC12") (pin "2") (pinfunction "VSS_2") (pintype "passive"))
      (node (ref "IC12") (pin "5") (pinfunction "WP_5") (pintype "input"))
      (node (ref "IC3") (pin "12") (pinfunction "DGND0_12") (pintype "bidirectional"))
      (node (ref "IC3") (pin "13") (pinfunction "DGND_13") (pintype "bidirectional"))
      (node (ref "IC5") (pin "11") (pinfunction "VSS_11") (pintype "power_in"))
      (node (ref "IC5") (pin "27") (pinfunction "VSS1_27") (pintype "power_in"))
      (node (ref "ICSP") (pin "5") (pinfunction "5_5") (pintype "passive"))
      (node (ref "JP15") (pin "1") (pinfunction "1_1") (pintype "passive"))
      (node (ref "R42") (pin "1") (pinfunction "1_1") (pintype "passive"))
      (node (ref "R44") (pin "1") (pinfunction "1_1") (pintype "passive"))
    )
    (net (code "49") (name "Net-(D1-PadA)") (class "Default")
      (node (ref "D1") (pin "A") (pinfunction "A_A") (pintype "passive"))
      (node (ref "F1") (pin "1") (pinfunction "1_1") (pintype "passive"))
    )
    (net (code "50") (name "Net-(D2-PadC)") (class "Default")
      (node (ref "D2") (pin "C") (pinfunction "C_C") (pintype "passive"))
      (node (ref "F2") (pin "1") (pinfunction "1_1") (pintype "passive"))
    )
    (net (code "51") (name "Net-(D3-P$1)") (class "Default")
      (node (ref "D3") (pin "C") (pinfunction "P$1_C") (pintype "bidirectional"))
      (node (ref "IC11") (pin "3") (pinfunction "C_3") (pintype "passive"))
      (node (ref "R31") (pin "1") (pinfunction "1_1") (pintype "passive"))
      (node (ref "R32") (pin "1") (pinfunction "1_1") (pintype "passive"))
    )
    (net (code "52") (name "Net-(D3-P$2)") (class "Default")
      (node (ref "D3") (pin "A") (pinfunction "P$2_A") (pintype "bidirectional"))
      (node (ref "IC11") (pin "2") (pinfunction "A_2") (pintype "passive"))
      (node (ref "R29") (pin "2") (pinfunction "2_2") (pintype "passive"))
      (node (ref "R30") (pin "2") (pinfunction "2_2") (pintype "passive"))
    )
    (net (code "53") (name "Net-(F1-Pad2)") (class "Default")
      (node (ref "F1") (pin "2") (pinfunction "2_2") (pintype "passive"))
      (node (ref "PWR") (pin "1") (pinfunction "1_1") (pintype "passive"))
      (node (ref "PWR") (pin "2") (pinfunction "2_2") (pintype "passive"))
    )
    (net (code "54") (name "Net-(F2-Pad2)") (class "Default")
      (node (ref "F2") (pin "2") (pinfunction "2_2") (pintype "passive"))
      (node (ref "PWR") (pin "10") (pinfunction "10_10") (pintype "passive"))
      (node (ref "PWR") (pin "9") (pinfunction "9_9") (pintype "passive"))
    )
    (net (code "55") (name "Net-(IC1A--IN)") (class "Default")
      (node (ref "IC1") (pin "2") (pinfunction "-IN_2") (pintype "input"))
      (node (ref "R1") (pin "2") (pinfunction "2_2") (pintype "passive"))
      (node (ref "R2") (pin "1") (pinfunction "1_1") (pintype "passive"))
    )
    (net (code "56") (name "Net-(IC1A-OUT)") (class "Default")
      (node (ref "C1") (pin "1") (pinfunction "1_1") (pintype "passive"))
      (node (ref "IC1") (pin "1") (pinfunction "OUT_1") (pintype "output"))
      (node (ref "R3") (pin "1") (pinfunction "1_1") (pintype "passive"))
    )
    (net (code "57") (name "Net-(IC1B--IN)") (class "Default")
      (node (ref "IC1") (pin "6") (pinfunction "-IN_6") (pintype "input"))
      (node (ref "R4") (pin "2") (pinfunction "2_2") (pintype "passive"))
      (node (ref "R5") (pin "1") (pinfunction "1_1") (pintype "passive"))
    )
    (net (code "58") (name "Net-(IC1B-OUT)") (class "Default")
      (node (ref "C2") (pin "1") (pinfunction "1_1") (pintype "passive"))
      (node (ref "IC1") (pin "7") (pinfunction "OUT_7") (pintype "output"))
      (node (ref "R6") (pin "1") (pinfunction "1_1") (pintype "passive"))
    )
    (net (code "59") (name "Net-(IC1C--IN)") (class "Default")
      (node (ref "IC1") (pin "9") (pinfunction "-IN_9") (pintype "input"))
      (node (ref "R11") (pin "1") (pinfunction "1_1") (pintype "passive"))
      (node (ref "R12") (pin "2") (pinfunction "2_2") (pintype "passive"))
    )
    (net (code "60") (name "Net-(IC1C-OUT)") (class "Default")
      (node (ref "C6") (pin "1") (pinfunction "1_1") (pintype "passive"))
      (node (ref "IC1") (pin "8") (pinfunction "OUT_8") (pintype "output"))
      (node (ref "R10") (pin "1") (pinfunction "1_1") (pintype "passive"))
    )
    (net (code "61") (name "Net-(IC1D--IN)") (class "Default")
      (node (ref "IC1") (pin "13") (pinfunction "-IN_13") (pintype "input"))
      (node (ref "R8") (pin "1") (pinfunction "1_1") (pintype "passive"))
      (node (ref "R9") (pin "2") (pinfunction "2_2") (pintype "passive"))
    )
    (net (code "62") (name "Net-(IC1D-OUT)") (class "Default")
      (node (ref "C4") (pin "1") (pinfunction "1_1") (pintype "passive"))
      (node (ref "IC1") (pin "14") (pinfunction "OUT_14") (pintype "output"))
      (node (ref "R7") (pin "1") (pinfunction "1_1") (pintype "passive"))
    )
    (net (code "63") (name "Net-(IC2A--IN)") (class "Default")
      (node (ref "IC2") (pin "2") (pinfunction "-IN_2") (pintype "input"))
      (node (ref "R13") (pin "2") (pinfunction "2_2") (pintype "passive"))
      (node (ref "R15") (pin "1") (pinfunction "1_1") (pintype "passive"))
    )
    (net (code "64") (name "Net-(IC2A-OUT)") (class "Default")
      (node (ref "IC2") (pin "1") (pinfunction "OUT_1") (pintype "output"))
      (node (ref "R14") (pin "1") (pinfunction "1_1") (pintype "passive"))
      (node (ref "R15") (pin "2") (pinfunction "2_2") (pintype "passive"))
    )
    (net (code "65") (name "Net-(IC2B--IN)") (class "Default")
      (node (ref "IC2") (pin "6") (pinfunction "-IN_6") (pintype "input"))
      (node (ref "R16") (pin "2") (pinfunction "2_2") (pintype "passive"))
      (node (ref "R18") (pin "1") (pinfunction "1_1") (pintype "passive"))
    )
    (net (code "66") (name "Net-(IC2B-OUT)") (class "Default")
      (node (ref "IC2") (pin "7") (pinfunction "OUT_7") (pintype "output"))
      (node (ref "R17") (pin "1") (pinfunction "1_1") (pintype "passive"))
      (node (ref "R18") (pin "2") (pinfunction "2_2") (pintype "passive"))
    )
    (net (code "67") (name "Net-(IC2C--IN)") (class "Default")
      (node (ref "IC2") (pin "9") (pinfunction "-IN_9") (pintype "input"))
      (node (ref "R17") (pin "2") (pinfunction "2_2") (pintype "passive"))
      (node (ref "R20") (pin "1") (pinfunction "1_1") (pintype "passive"))
    )
    (net (code "68") (name "Net-(IC2D--IN)") (class "Default")
      (node (ref "IC2") (pin "13") (pinfunction "-IN_13") (pintype "input"))
      (node (ref "R14") (pin "2") (pinfunction "2_2") (pintype "passive"))
      (node (ref "R19") (pin "1") (pinfunction "1_1") (pintype "passive"))
    )
    (net (code "69") (name "Net-(IC4A--IN)") (class "Default")
      (node (ref "IC4") (pin "2") (pinfunction "-IN_2") (pintype "input"))
      (node (ref "R21") (pin "1") (pinfunction "1_1") (pintype "passive"))
      (node (ref "R24") (pin "2") (pinfunction "2_2") (pintype "passive"))
    )
    (net (code "70") (name "Net-(IC4B--IN)") (class "Default")
      (node (ref "IC4") (pin "6") (pinfunction "-IN_6") (pintype "input"))
      (node (ref "R22") (pin "1") (pinfunction "1_1") (pintype "passive"))
      (node (ref "R27") (pin "2") (pinfunction "2_2") (pintype "passive"))
    )
    (net (code "71") (name "Net-(IC4C--IN)") (class "Default")
      (node (ref "IC4") (pin "9") (pinfunction "-IN_9") (pintype "input"))
      (node (ref "R26") (pin "1") (pinfunction "1_1") (pintype "passive"))
      (node (ref "R28") (pin "2") (pinfunction "2_2") (pintype "passive"))
    )
    (net (code "72") (name "Net-(IC4C-OUT)") (class "Default")
      (node (ref "IC4") (pin "8") (pinfunction "OUT_8") (pintype "output"))
      (node (ref "R26") (pin "2") (pinfunction "2_2") (pintype "passive"))
      (node (ref "R27") (pin "1") (pinfunction "1_1") (pintype "passive"))
    )
    (net (code "73") (name "Net-(IC4D--IN)") (class "Default")
      (node (ref "IC4") (pin "13") (pinfunction "-IN_13") (pintype "input"))
      (node (ref "R23") (pin "1") (pinfunction "1_1") (pintype "passive"))
      (node (ref "R25") (pin "2") (pinfunction "2_2") (pintype "passive"))
    )
    (net (code "74") (name "Net-(IC4D-OUT)") (class "Default")
      (node (ref "IC4") (pin "14") (pinfunction "OUT_14") (pintype "output"))
      (node (ref "R23") (pin "2") (pinfunction "2_2") (pintype "passive"))
      (node (ref "R24") (pin "1") (pinfunction "1_1") (pintype "passive"))
    )
    (net (code "75") (name "Net-(IC5-PTB4)") (class "Default")
      (node (ref "IC5") (pin "13") (pinfunction "PTB4_13") (pintype "bidirectional"))
      (node (ref "PB4") (pin "TP") (pinfunction "TP_TP") (pintype "input"))
    )
    (net (code "76") (name "Net-(IC5-PTB5)") (class "Default")
      (node (ref "IC5") (pin "12") (pinfunction "PTB5_12") (pintype "bidirectional"))
      (node (ref "PB5") (pin "TP") (pinfunction "TP_TP") (pintype "input"))
    )
    (net (code "77") (name "Net-(IC5-PTD5)") (class "Default")
      (node (ref "IC5") (pin "18") (pinfunction "PTD5_18") (pintype "bidirectional"))
      (node (ref "PD5") (pin "TP") (pinfunction "TP_TP") (pintype "input"))
    )
    (net (code "78") (name "Net-(IC5-PTD6)") (class "Default")
      (node (ref "IC5") (pin "17") (pinfunction "PTD6_17") (pintype "bidirectional"))
      (node (ref "PD6") (pin "TP") (pinfunction "TP_TP") (pintype "input"))
    )
    (net (code "79") (name "Net-(IC5-PTD7)") (class "Default")
      (node (ref "IC5") (pin "16") (pinfunction "PTD7_16") (pintype "bidirectional"))
      (node (ref "PD7") (pin "TP") (pinfunction "TP_TP") (pintype "input"))
    )
    (net (code "80") (name "Net-(IC6A--IN)") (class "Default")
      (node (ref "IC6") (pin "2") (pinfunction "-IN_2") (pintype "input"))
      (node (ref "R33") (pin "2") (pinfunction "2_2") (pintype "passive"))
      (node (ref "R34") (pin "1") (pinfunction "1_1") (pintype "passive"))
    )
    (net (code "81") (name "Net-(IC6B--IN)") (class "Default")
      (node (ref "IC6") (pin "6") (pinfunction "-IN_6") (pintype "input"))
      (node (ref "R35") (pin "2") (pinfunction "2_2") (pintype "passive"))
      (node (ref "R36") (pin "1") (pinfunction "1_1") (pintype "passive"))
    )
    (net (code "82") (name "Net-(IC6C-+IN)") (class "Default")
      (node (ref "C22") (pin "1") (pinfunction "1_1") (pintype "passive"))
      (node (ref "IC6") (pin "10") (pinfunction "+IN_10") (pintype "input"))
      (node (ref "R40") (pin "2") (pinfunction "2_2") (pintype "passive"))
      (node (ref "R41") (pin "1") (pinfunction "1_1") (pintype "passive"))
    )
    (net (code "83") (name "Net-(IC6D--IN)") (class "Default")
      (node (ref "IC6") (pin "13") (pinfunction "-IN_13") (pintype "input"))
      (node (ref "R38") (pin "1") (pinfunction "1_1") (pintype "passive"))
      (node (ref "R39") (pin "2") (pinfunction "2_2") (pintype "passive"))
    )
    (net (code "84") (name "Net-(IC6D-OUT)") (class "Default")
      (node (ref "C21") (pin "1") (pinfunction "1_1") (pintype "passive"))
      (node (ref "IC6") (pin "14") (pinfunction "OUT_14") (pintype "output"))
      (node (ref "R37") (pin "1") (pinfunction "1_1") (pintype "passive"))
    )
    (net (code "85") (name "Net-(IC8-FILTER)") (class "Default")
      (node (ref "C27") (pin "1") (pinfunction "1_1") (pintype "passive"))
      (node (ref "IC8") (pin "1") (pinfunction "FILTER_1") (pintype "bidirectional"))
    )
    (net (code "86") (name "Net-(IC11-VB)") (class "Default")
      (node (ref "IC11") (pin "7") (pinfunction "VB_7") (pintype "passive"))
      (node (ref "R42") (pin "2") (pinfunction "2_2") (pintype "passive"))
    )
    (net (code "87") (name "Net-(IN1-2)") (class "Default")
      (node (ref "IN1") (pin "P$1") (pinfunction "2_P$1") (pintype "passive"))
      (node (ref "R25") (pin "1") (pinfunction "1_1") (pintype "passive"))
    )
    (net (code "88") (name "Net-(IN2-2)") (class "Default")
      (node (ref "IN2") (pin "P$1") (pinfunction "2_P$1") (pintype "passive"))
      (node (ref "R28") (pin "1") (pinfunction "1_1") (pintype "passive"))
    )
    (net (code "89") (name "Net-(IN3-2)") (class "Default")
      (node (ref "IN3") (pin "P$1") (pinfunction "2_P$1") (pintype "passive"))
      (node (ref "R33") (pin "1") (pinfunction "1_1") (pintype "passive"))
    )
    (net (code "90") (name "Net-(IN4-2)") (class "Default")
      (node (ref "IN4") (pin "P$1") (pinfunction "2_P$1") (pintype "passive"))
      (node (ref "R13") (pin "1") (pinfunction "1_1") (pintype "passive"))
    )
    (net (code "91") (name "Net-(IN5-2)") (class "Default")
      (node (ref "IN5") (pin "P$1") (pinfunction "2_P$1") (pintype "passive"))
      (node (ref "R16") (pin "1") (pinfunction "1_1") (pintype "passive"))
    )
    (net (code "92") (name "Net-(IN6-2)") (class "Default")
      (node (ref "IN6") (pin "P$1") (pinfunction "2_P$1") (pintype "passive"))
      (node (ref "R35") (pin "1") (pinfunction "1_1") (pintype "passive"))
    )
    (net (code "93") (name "Net-(L2-P$1)") (class "Default")
      (node (ref "D2") (pin "A") (pinfunction "A_A") (pintype "passive"))
      (node (ref "L2") (pin "1") (pinfunction "P$1_1") (pintype "bidirectional"))
    )
    (net (code "94") (name "Net-(MIDI-3)") (class "Default")
      (node (ref "MIDI") (pin "R") (pinfunction "3_R") (pintype "bidirectional"))
      (node (ref "R30") (pin "1") (pinfunction "1_1") (pintype "passive"))
      (node (ref "R31") (pin "2") (pinfunction "2_2") (pintype "passive"))
    )
    (net (code "95") (name "Net-(MIDI-4)") (class "Default")
      (node (ref "MIDI") (pin "T") (pinfunction "4_T") (pintype "bidirectional"))
      (node (ref "R29") (pin "1") (pinfunction "1_1") (pintype "passive"))
      (node (ref "R32") (pin "2") (pinfunction "2_2") (pintype "passive"))
    )
    (net (code "96") (name "Net-(OUT1-2)") (class "Default")
      (node (ref "C6") (pin "2") (pinfunction "2_2") (pintype "passive"))
      (node (ref "OUT1") (pin "P$1") (pinfunction "2_P$1") (pintype "passive"))
      (node (ref "R10") (pin "2") (pinfunction "2_2") (pintype "passive"))
      (node (ref "R11") (pin "2") (pinfunction "2_2") (pintype "passive"))
    )
    (net (code "97") (name "Net-(OUT2-2)") (class "Default")
      (node (ref "C4") (pin "2") (pinfunction "2_2") (pintype "passive"))
      (node (ref "OUT2") (pin "P$1") (pinfunction "2_P$1") (pintype "passive"))
      (node (ref "R7") (pin "2") (pinfunction "2_2") (pintype "passive"))
      (node (ref "R8") (pin "2") (pinfunction "2_2") (pintype "passive"))
    )
    (net (code "98") (name "Net-(OUT3-2)") (class "Default")
      (node (ref "C2") (pin "2") (pinfunction "2_2") (pintype "passive"))
      (node (ref "OUT3") (pin "P$1") (pinfunction "2_P$1") (pintype "passive"))
      (node (ref "R5") (pin "2") (pinfunction "2_2") (pintype "passive"))
      (node (ref "R6") (pin "2") (pinfunction "2_2") (pintype "passive"))
    )
    (net (code "99") (name "Net-(OUT4-2)") (class "Default")
      (node (ref "C1") (pin "2") (pinfunction "2_2") (pintype "passive"))
      (node (ref "OUT4") (pin "P$1") (pinfunction "2_P$1") (pintype "passive"))
      (node (ref "R2") (pin "2") (pinfunction "2_2") (pintype "passive"))
      (node (ref "R3") (pin "2") (pinfunction "2_2") (pintype "passive"))
    )
    (net (code "100") (name "Net-(TRIG-2)") (class "Default")
      (node (ref "C21") (pin "2") (pinfunction "2_2") (pintype "passive"))
      (node (ref "R37") (pin "2") (pinfunction "2_2") (pintype "passive"))
      (node (ref "R38") (pin "2") (pinfunction "2_2") (pintype "passive"))
      (node (ref "TRIG") (pin "P$1") (pinfunction "2_P$1") (pintype "passive"))
    )
    (net (code "101") (name "VDD") (class "Default")
      (node (ref "C11") (pin "1") (pinfunction "1_1") (pintype "passive"))
      (node (ref "C18") (pin "2") (pinfunction "2_2") (pintype "passive"))
      (node (ref "C19") (pin "1") (pinfunction "1_1") (pintype "passive"))
      (node (ref "C26") (pin "1") (pinfunction "1_1") (pintype "passive"))
      (node (ref "C33") (pin "+") (pinfunction "+_+") (pintype "passive"))
      (node (ref "C34") (pin "1") (pinfunction "1_1") (pintype "passive"))
      (node (ref "IC10") (pin "2") (pinfunction "VOUT_2") (pintype "output"))
      (node (ref "IC11") (pin "8") (pinfunction "VCC_8") (pintype "passive"))
      (node (ref "IC3") (pin "14") (pinfunction "DVDD0_14") (pintype "bidirectional"))
      (node (ref "IC3") (pin "15") (pinfunction "DVDD_15") (pintype "bidirectional"))
      (node (ref "IC5") (pin "28") (pinfunction "VDD1_28") (pintype "power_in"))
      (node (ref "IC5") (pin "5") (pinfunction "VDD_5") (pintype "power_in"))
      (node (ref "IC7") (pin "4") (pinfunction "DVDD_4") (pintype "bidirectional"))
      (node (ref "ICSP") (pin "1") (pinfunction "1_1") (pintype "passive"))
      (node (ref "JP14") (pin "1") (pinfunction "1_1") (pintype "passive"))
      (node (ref "R43") (pin "1") (pinfunction "1_1") (pintype "passive"))
    )
    (net (code "102") (name "unconnected-(IC7-REFO-Pad16)") (class "Default")
      (node (ref "IC7") (pin "16") (pinfunction "REFO_16") (pintype "bidirectional"))
    )
    (net (code "103") (name "unconnected-(MIDI-2-PadS)") (class "Default")
      (node (ref "MIDI") (pin "S") (pinfunction "2_S") (pintype "bidirectional"))
    )
    (net (code "104") (name "unconnected-(OUT1-3-PadP$2)") (class "Default")
      (node (ref "OUT1") (pin "P$2") (pinfunction "3_P$2") (pintype "passive"))
    )
    (net (code "105") (name "unconnected-(OUT2-3-PadP$2)") (class "Default")
      (node (ref "OUT2") (pin "P$2") (pinfunction "3_P$2") (pintype "passive"))
    )
    (net (code "106") (name "unconnected-(OUT3-3-PadP$2)") (class "Default")
      (node (ref "OUT3") (pin "P$2") (pinfunction "3_P$2") (pintype "passive"))
    )
    (net (code "107") (name "unconnected-(OUT4-3-PadP$2)") (class "Default")
      (node (ref "OUT4") (pin "P$2") (pinfunction "3_P$2") (pintype "passive"))
    )
    (net (code "108") (name "unconnected-(TRIG-3-PadP$2)") (class "Default")
      (node (ref "TRIG") (pin "P$2") (pinfunction "3_P$2") (pintype "passive"))
    )
  )
)
